# 12_-_REFERENCE_CLOCKS.net
KiCad netlist of a schematic drawn in Altium Designer
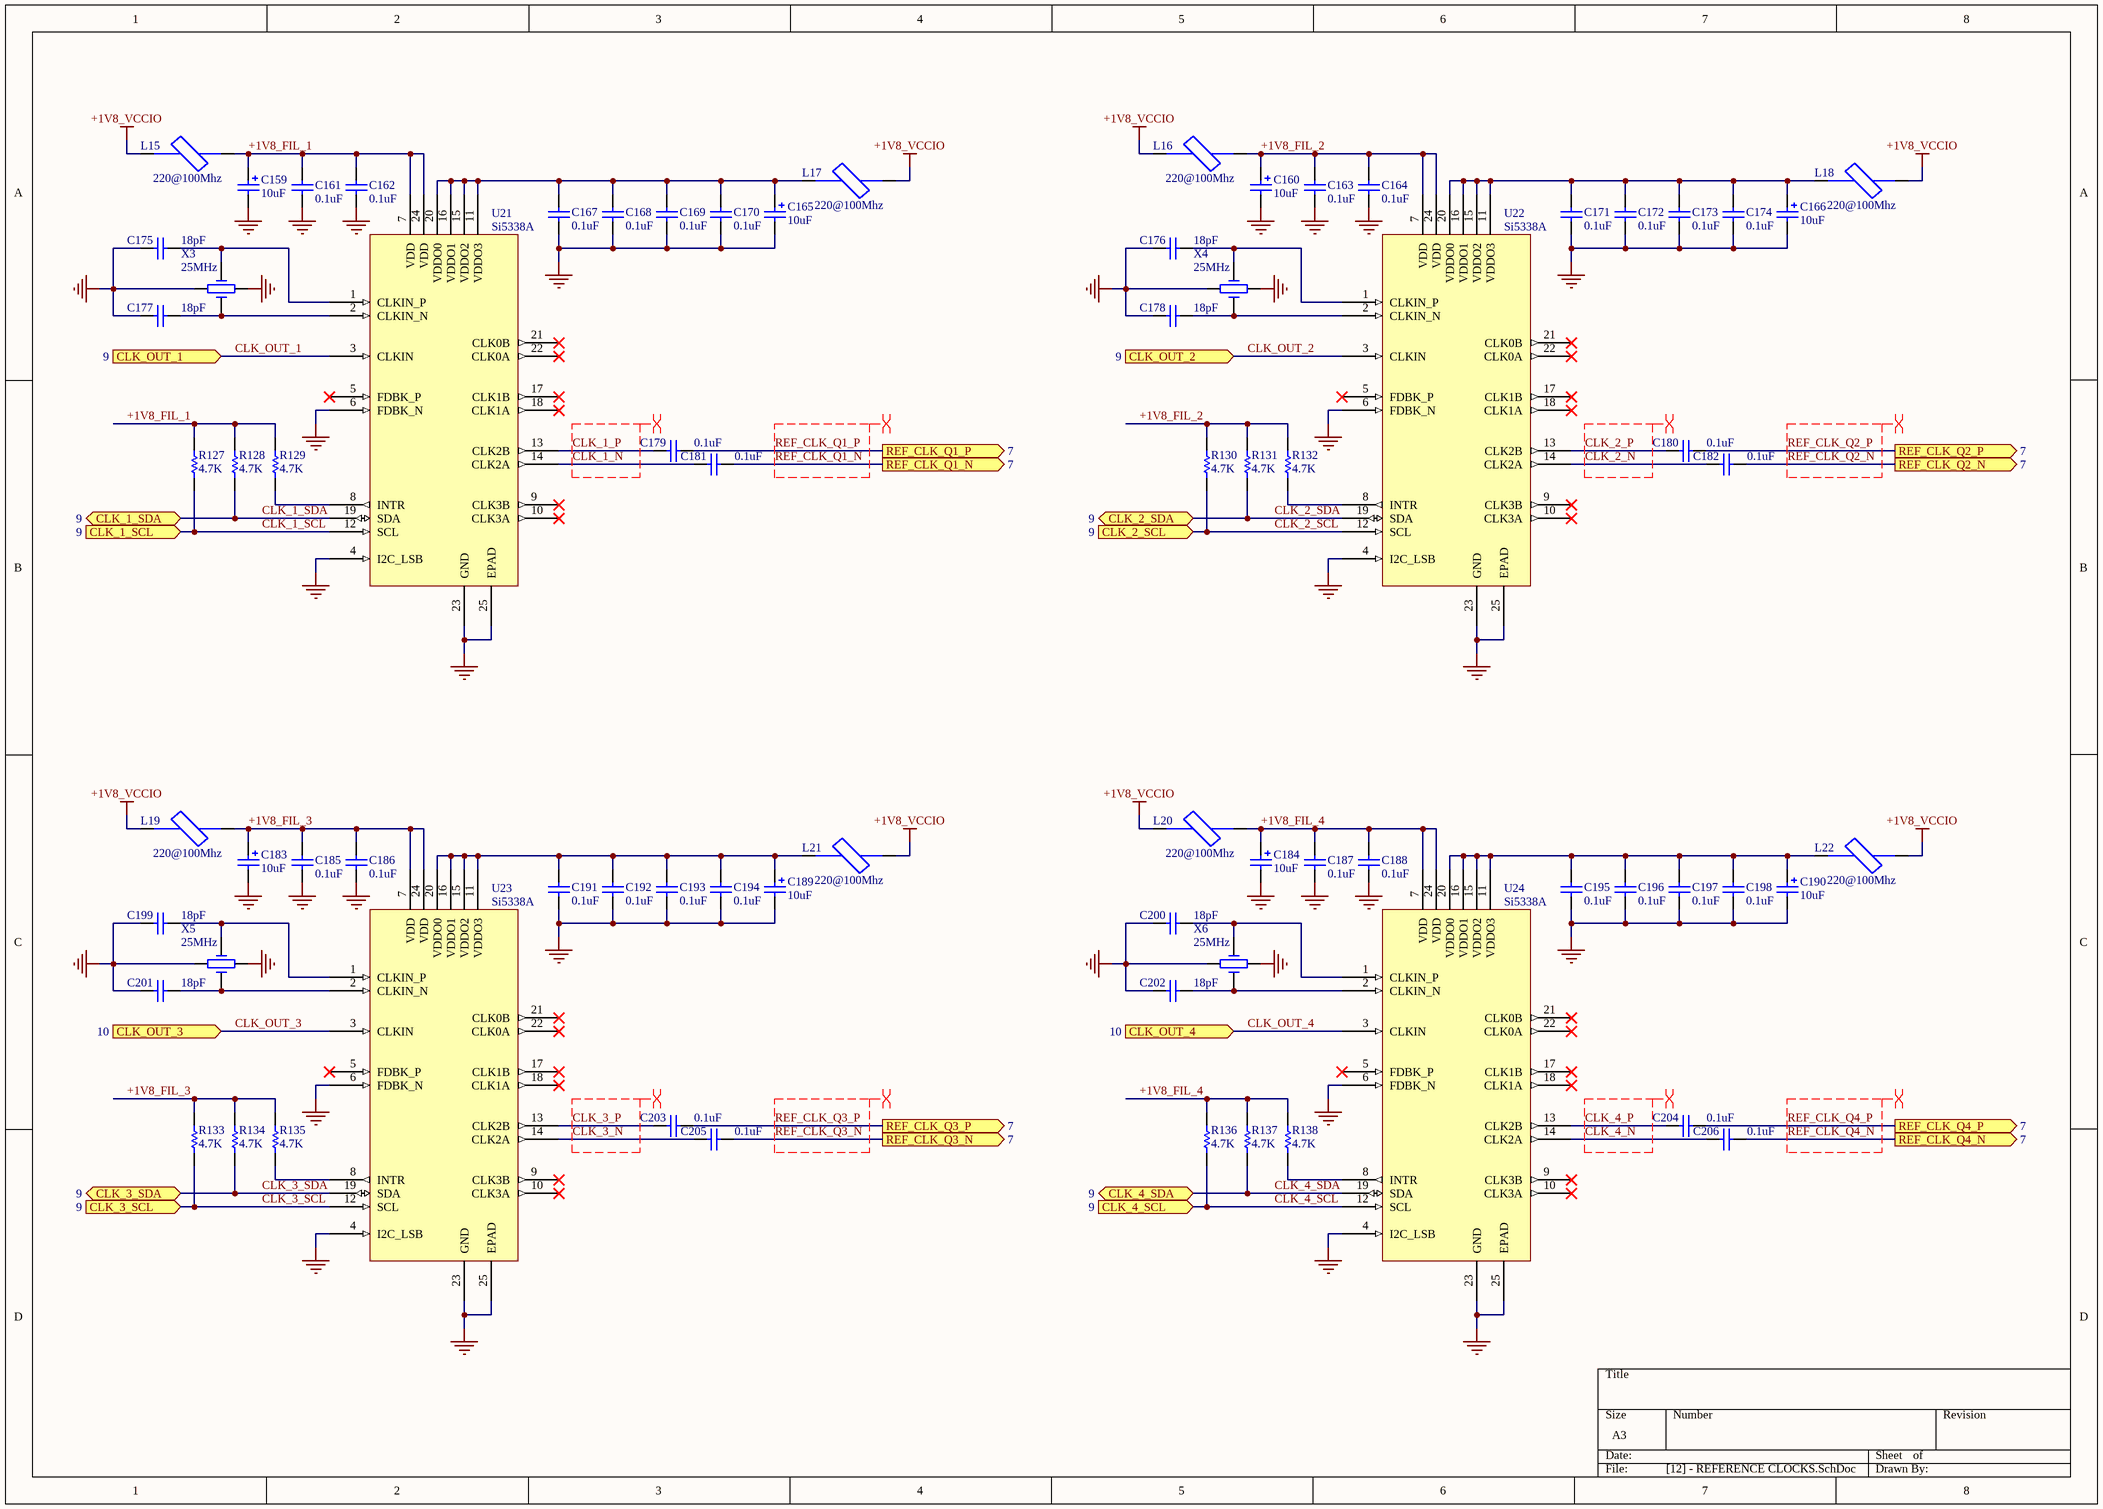
[diagram p0: [12] - REFERENCE CLOCKS.SchDoc]

(export (version "E")
  (design (tool "Eeschema 10.0.6"))
  (components
    (comp (ref "C159")
      (value "10uF")
      (footprint "TANT_B")
      (description "Tantalum Polarized Capacitor")
      (libsource (lib "Passive Components") (part "Cap Tant"))
    )
    (comp (ref "C160")
      (value "10uF")
      (footprint "TANT_B")
      (description "Tantalum Polarized Capacitor")
      (libsource (lib "Passive Components") (part "Cap Tant"))
    )
    (comp (ref "C161")
      (value "0.1uF")
      (footprint "0402_C")
      (description "Non-Pol SMD Capacitor")
      (libsource (lib "Passive Components") (part "Cap SMD"))
    )
    (comp (ref "C162")
      (value "0.1uF")
      (footprint "0402_C")
      (description "Non-Pol SMD Capacitor")
      (libsource (lib "Passive Components") (part "Cap SMD"))
    )
    (comp (ref "C163")
      (value "0.1uF")
      (footprint "0402_C")
      (description "Non-Pol SMD Capacitor")
      (libsource (lib "Passive Components") (part "Cap SMD"))
    )
    (comp (ref "C164")
      (value "0.1uF")
      (footprint "0402_C")
      (description "Non-Pol SMD Capacitor")
      (libsource (lib "Passive Components") (part "Cap SMD"))
    )
    (comp (ref "C165")
      (value "10uF")
      (footprint "TANT_B")
      (description "Tantalum Polarized Capacitor")
      (libsource (lib "Passive Components") (part "Cap Tant"))
    )
    (comp (ref "C166")
      (value "10uF")
      (footprint "TANT_B")
      (description "Tantalum Polarized Capacitor")
      (libsource (lib "Passive Components") (part "Cap Tant"))
    )
    (comp (ref "C167")
      (value "0.1uF")
      (footprint "0402_C")
      (description "Non-Pol SMD Capacitor")
      (libsource (lib "Passive Components") (part "Cap SMD"))
    )
    (comp (ref "C168")
      (value "0.1uF")
      (footprint "0402_C")
      (description "Non-Pol SMD Capacitor")
      (libsource (lib "Passive Components") (part "Cap SMD"))
    )
    (comp (ref "C169")
      (value "0.1uF")
      (footprint "0402_C")
      (description "Non-Pol SMD Capacitor")
      (libsource (lib "Passive Components") (part "Cap SMD"))
    )
    (comp (ref "C170")
      (value "0.1uF")
      (footprint "0402_C")
      (description "Non-Pol SMD Capacitor")
      (libsource (lib "Passive Components") (part "Cap SMD"))
    )
    (comp (ref "C171")
      (value "0.1uF")
      (footprint "0402_C")
      (description "Non-Pol SMD Capacitor")
      (libsource (lib "Passive Components") (part "Cap SMD"))
    )
    (comp (ref "C172")
      (value "0.1uF")
      (footprint "0402_C")
      (description "Non-Pol SMD Capacitor")
      (libsource (lib "Passive Components") (part "Cap SMD"))
    )
    (comp (ref "C173")
      (value "0.1uF")
      (footprint "0402_C")
      (description "Non-Pol SMD Capacitor")
      (libsource (lib "Passive Components") (part "Cap SMD"))
    )
    (comp (ref "C174")
      (value "0.1uF")
      (footprint "0402_C")
      (description "Non-Pol SMD Capacitor")
      (libsource (lib "Passive Components") (part "Cap SMD"))
    )
    (comp (ref "C175")
      (value "18pF")
      (footprint "0402_C")
      (description "Non-Pol SMD Capacitor")
      (libsource (lib "Passive Components") (part "Cap SMD"))
    )
    (comp (ref "C176")
      (value "18pF")
      (footprint "0402_C")
      (description "Non-Pol SMD Capacitor")
      (libsource (lib "Passive Components") (part "Cap SMD"))
    )
    (comp (ref "C177")
      (value "18pF")
      (footprint "0402_C")
      (description "Non-Pol SMD Capacitor")
      (libsource (lib "Passive Components") (part "Cap SMD"))
    )
    (comp (ref "C178")
      (value "18pF")
      (footprint "0402_C")
      (description "Non-Pol SMD Capacitor")
      (libsource (lib "Passive Components") (part "Cap SMD"))
    )
    (comp (ref "C179")
      (value "0.1uF")
      (footprint "0402_C")
      (description "Non-Pol SMD Capacitor")
      (libsource (lib "Passive Components") (part "Cap SMD"))
    )
    (comp (ref "C180")
      (value "0.1uF")
      (footprint "0402_C")
      (description "Non-Pol SMD Capacitor")
      (libsource (lib "Passive Components") (part "Cap SMD"))
    )
    (comp (ref "C181")
      (value "0.1uF")
      (footprint "0402_C")
      (description "Non-Pol SMD Capacitor")
      (libsource (lib "Passive Components") (part "Cap SMD"))
    )
    (comp (ref "C182")
      (value "0.1uF")
      (footprint "0402_C")
      (description "Non-Pol SMD Capacitor")
      (libsource (lib "Passive Components") (part "Cap SMD"))
    )
    (comp (ref "C183")
      (value "10uF")
      (footprint "TANT_B")
      (description "Tantalum Polarized Capacitor")
      (libsource (lib "Passive Components") (part "Cap Tant"))
    )
    (comp (ref "C184")
      (value "10uF")
      (footprint "TANT_B")
      (description "Tantalum Polarized Capacitor")
      (libsource (lib "Passive Components") (part "Cap Tant"))
    )
    (comp (ref "C185")
      (value "0.1uF")
      (footprint "0402_C")
      (description "Non-Pol SMD Capacitor")
      (libsource (lib "Passive Components") (part "Cap SMD"))
    )
    (comp (ref "C186")
      (value "0.1uF")
      (footprint "0402_C")
      (description "Non-Pol SMD Capacitor")
      (libsource (lib "Passive Components") (part "Cap SMD"))
    )
    (comp (ref "C187")
      (value "0.1uF")
      (footprint "0402_C")
      (description "Non-Pol SMD Capacitor")
      (libsource (lib "Passive Components") (part "Cap SMD"))
    )
    (comp (ref "C188")
      (value "0.1uF")
      (footprint "0402_C")
      (description "Non-Pol SMD Capacitor")
      (libsource (lib "Passive Components") (part "Cap SMD"))
    )
    (comp (ref "C189")
      (value "10uF")
      (footprint "TANT_B")
      (description "Tantalum Polarized Capacitor")
      (libsource (lib "Passive Components") (part "Cap Tant"))
    )
    (comp (ref "C190")
      (value "10uF")
      (footprint "TANT_B")
      (description "Tantalum Polarized Capacitor")
      (libsource (lib "Passive Components") (part "Cap Tant"))
    )
    (comp (ref "C191")
      (value "0.1uF")
      (footprint "0402_C")
      (description "Non-Pol SMD Capacitor")
      (libsource (lib "Passive Components") (part "Cap SMD"))
    )
    (comp (ref "C192")
      (value "0.1uF")
      (footprint "0402_C")
      (description "Non-Pol SMD Capacitor")
      (libsource (lib "Passive Components") (part "Cap SMD"))
    )
    (comp (ref "C193")
      (value "0.1uF")
      (footprint "0402_C")
      (description "Non-Pol SMD Capacitor")
      (libsource (lib "Passive Components") (part "Cap SMD"))
    )
    (comp (ref "C194")
      (value "0.1uF")
      (footprint "0402_C")
      (description "Non-Pol SMD Capacitor")
      (libsource (lib "Passive Components") (part "Cap SMD"))
    )
    (comp (ref "C195")
      (value "0.1uF")
      (footprint "0402_C")
      (description "Non-Pol SMD Capacitor")
      (libsource (lib "Passive Components") (part "Cap SMD"))
    )
    (comp (ref "C196")
      (value "0.1uF")
      (footprint "0402_C")
      (description "Non-Pol SMD Capacitor")
      (libsource (lib "Passive Components") (part "Cap SMD"))
    )
    (comp (ref "C197")
      (value "0.1uF")
      (footprint "0402_C")
      (description "Non-Pol SMD Capacitor")
      (libsource (lib "Passive Components") (part "Cap SMD"))
    )
    (comp (ref "C198")
      (value "0.1uF")
      (footprint "0402_C")
      (description "Non-Pol SMD Capacitor")
      (libsource (lib "Passive Components") (part "Cap SMD"))
    )
    (comp (ref "C199")
      (value "18pF")
      (footprint "0402_C")
      (description "Non-Pol SMD Capacitor")
      (libsource (lib "Passive Components") (part "Cap SMD"))
    )
    (comp (ref "C200")
      (value "18pF")
      (footprint "0402_C")
      (description "Non-Pol SMD Capacitor")
      (libsource (lib "Passive Components") (part "Cap SMD"))
    )
    (comp (ref "C201")
      (value "18pF")
      (footprint "0402_C")
      (description "Non-Pol SMD Capacitor")
      (libsource (lib "Passive Components") (part "Cap SMD"))
    )
    (comp (ref "C202")
      (value "18pF")
      (footprint "0402_C")
      (description "Non-Pol SMD Capacitor")
      (libsource (lib "Passive Components") (part "Cap SMD"))
    )
    (comp (ref "C203")
      (value "0.1uF")
      (footprint "0402_C")
      (description "Non-Pol SMD Capacitor")
      (libsource (lib "Passive Components") (part "Cap SMD"))
    )
    (comp (ref "C204")
      (value "0.1uF")
      (footprint "0402_C")
      (description "Non-Pol SMD Capacitor")
      (libsource (lib "Passive Components") (part "Cap SMD"))
    )
    (comp (ref "C205")
      (value "0.1uF")
      (footprint "0402_C")
      (description "Non-Pol SMD Capacitor")
      (libsource (lib "Passive Components") (part "Cap SMD"))
    )
    (comp (ref "C206")
      (value "0.1uF")
      (footprint "0402_C")
      (description "Non-Pol SMD Capacitor")
      (libsource (lib "Passive Components") (part "Cap SMD"))
    )
    (comp (ref "L15")
      (value "220@100Mhz")
      (footprint "0805_L")
      (description "Ferrite Bead")
      (libsource (lib "Passive Components") (part "Ferrite Bead"))
    )
    (comp (ref "L16")
      (value "220@100Mhz")
      (footprint "0805_L")
      (description "Ferrite Bead")
      (libsource (lib "Passive Components") (part "Ferrite Bead"))
    )
    (comp (ref "L17")
      (value "220@100Mhz")
      (footprint "0805_L")
      (description "Ferrite Bead")
      (libsource (lib "Passive Components") (part "Ferrite Bead"))
    )
    (comp (ref "L18")
      (value "220@100Mhz")
      (footprint "0805_L")
      (description "Ferrite Bead")
      (libsource (lib "Passive Components") (part "Ferrite Bead"))
    )
    (comp (ref "L19")
      (value "220@100Mhz")
      (footprint "0805_L")
      (description "Ferrite Bead")
      (libsource (lib "Passive Components") (part "Ferrite Bead"))
    )
    (comp (ref "L20")
      (value "220@100Mhz")
      (footprint "0805_L")
      (description "Ferrite Bead")
      (libsource (lib "Passive Components") (part "Ferrite Bead"))
    )
    (comp (ref "L21")
      (value "220@100Mhz")
      (footprint "0805_L")
      (description "Ferrite Bead")
      (libsource (lib "Passive Components") (part "Ferrite Bead"))
    )
    (comp (ref "L22")
      (value "220@100Mhz")
      (footprint "0805_L")
      (description "Ferrite Bead")
      (libsource (lib "Passive Components") (part "Ferrite Bead"))
    )
    (comp (ref "R127")
      (value "4.7K")
      (footprint "0402_R")
      (description "SMD Resistor")
      (fields (field (name "TOLERANCE") "5%"))
      (libsource (lib "Passive Components") (part "Res SMD"))
    )
    (comp (ref "R128")
      (value "4.7K")
      (footprint "0402_R")
      (description "SMD Resistor")
      (fields (field (name "TOLERANCE") "5%"))
      (libsource (lib "Passive Components") (part "Res SMD"))
    )
    (comp (ref "R129")
      (value "4.7K")
      (footprint "0402_R")
      (description "SMD Resistor")
      (fields (field (name "TOLERANCE") "5%"))
      (libsource (lib "Passive Components") (part "Res SMD"))
    )
    (comp (ref "R130")
      (value "4.7K")
      (footprint "0402_R")
      (description "SMD Resistor")
      (fields (field (name "TOLERANCE") "5%"))
      (libsource (lib "Passive Components") (part "Res SMD"))
    )
    (comp (ref "R131")
      (value "4.7K")
      (footprint "0402_R")
      (description "SMD Resistor")
      (fields (field (name "TOLERANCE") "5%"))
      (libsource (lib "Passive Components") (part "Res SMD"))
    )
    (comp (ref "R132")
      (value "4.7K")
      (footprint "0402_R")
      (description "SMD Resistor")
      (fields (field (name "TOLERANCE") "5%"))
      (libsource (lib "Passive Components") (part "Res SMD"))
    )
    (comp (ref "R133")
      (value "4.7K")
      (footprint "0402_R")
      (description "SMD Resistor")
      (fields (field (name "TOLERANCE") "5%"))
      (libsource (lib "Passive Components") (part "Res SMD"))
    )
    (comp (ref "R134")
      (value "4.7K")
      (footprint "0402_R")
      (description "SMD Resistor")
      (fields (field (name "TOLERANCE") "5%"))
      (libsource (lib "Passive Components") (part "Res SMD"))
    )
    (comp (ref "R135")
      (value "4.7K")
      (footprint "0402_R")
      (description "SMD Resistor")
      (fields (field (name "TOLERANCE") "5%"))
      (libsource (lib "Passive Components") (part "Res SMD"))
    )
    (comp (ref "R136")
      (value "4.7K")
      (footprint "0402_R")
      (description "SMD Resistor")
      (fields (field (name "TOLERANCE") "5%"))
      (libsource (lib "Passive Components") (part "Res SMD"))
    )
    (comp (ref "R137")
      (value "4.7K")
      (footprint "0402_R")
      (description "SMD Resistor")
      (fields (field (name "TOLERANCE") "5%"))
      (libsource (lib "Passive Components") (part "Res SMD"))
    )
    (comp (ref "R138")
      (value "4.7K")
      (footprint "0402_R")
      (description "SMD Resistor")
      (fields (field (name "TOLERANCE") "5%"))
      (libsource (lib "Passive Components") (part "Res SMD"))
    )
    (comp (ref "U21")
      (value "Si5338A")
      (description "I2C-Programmable Any-Frequency, Any-Output Quad Clock Generator")
      (libsource (lib "Project_schlib") (part "Si5338"))
    )
    (comp (ref "U22")
      (value "Si5338A")
      (description "I2C-Programmable Any-Frequency, Any-Output Quad Clock Generator")
      (libsource (lib "Project_schlib") (part "Si5338"))
    )
    (comp (ref "U23")
      (value "Si5338A")
      (description "I2C-Programmable Any-Frequency, Any-Output Quad Clock Generator")
      (libsource (lib "Project_schlib") (part "Si5338"))
    )
    (comp (ref "U24")
      (value "Si5338A")
      (description "I2C-Programmable Any-Frequency, Any-Output Quad Clock Generator")
      (libsource (lib "Project_schlib") (part "Si5338"))
    )
    (comp (ref "X3")
      (value "25MHz")
      (footprint "OSC_3.2x2.5")
      (description "4-pin SMD Crystal")
      (fields (field (name "MANUFACTURER PART NUM") "ABM3B-25.000MHZ-D2Y-T"))
      (libsource (lib "Common Components") (part "XTAL 4pin"))
    )
    (comp (ref "X4")
      (value "25MHz")
      (footprint "OSC_3.2x2.5")
      (description "4-pin SMD Crystal")
      (fields (field (name "MANUFACTURER PART NUM") "ABM3B-25.000MHZ-D2Y-T"))
      (libsource (lib "Common Components") (part "XTAL 4pin"))
    )
    (comp (ref "X5")
      (value "25MHz")
      (footprint "OSC_3.2x2.5")
      (description "4-pin SMD Crystal")
      (fields (field (name "MANUFACTURER PART NUM") "ABM3B-25.000MHZ-D2Y-T"))
      (libsource (lib "Common Components") (part "XTAL 4pin"))
    )
    (comp (ref "X6")
      (value "25MHz")
      (footprint "OSC_3.2x2.5")
      (description "4-pin SMD Crystal")
      (fields (field (name "MANUFACTURER PART NUM") "ABM3B-25.000MHZ-D2Y-T"))
      (libsource (lib "Common Components") (part "XTAL 4pin"))
    )
  )
  (nets
    (net (code "1") (name "+1V8_VCCIO") (class "Default")
      (node (ref "L15") (pin "1") (pinfunction "1_1") (pintype "passive"))
      (node (ref "L16") (pin "1") (pinfunction "1_1") (pintype "passive"))
      (node (ref "L17") (pin "2") (pinfunction "2_2") (pintype "passive"))
      (node (ref "L18") (pin "2") (pinfunction "2_2") (pintype "passive"))
      (node (ref "L19") (pin "1") (pinfunction "1_1") (pintype "passive"))
      (node (ref "L20") (pin "1") (pinfunction "1_1") (pintype "passive"))
      (node (ref "L21") (pin "2") (pinfunction "2_2") (pintype "passive"))
      (node (ref "L22") (pin "2") (pinfunction "2_2") (pintype "passive"))
    )
    (net (code "2") (name "/+1V8_FIL_1") (class "Default")
      (node (ref "C159") (pin "1") (pinfunction "1_1") (pintype "passive"))
      (node (ref "C161") (pin "2") (pinfunction "2_2") (pintype "passive"))
      (node (ref "C162") (pin "2") (pinfunction "2_2") (pintype "passive"))
      (node (ref "L15") (pin "2") (pinfunction "2_2") (pintype "passive"))
      (node (ref "R127") (pin "2") (pinfunction "2_2") (pintype "passive"))
      (node (ref "R128") (pin "2") (pinfunction "2_2") (pintype "passive"))
      (node (ref "R129") (pin "2") (pinfunction "2_2") (pintype "passive"))
      (node (ref "U21") (pin "24") (pinfunction "VDD_24") (pintype "power_in"))
      (node (ref "U21") (pin "7") (pinfunction "VDD_7") (pintype "power_in"))
    )
    (net (code "3") (name "/+1V8_FIL_2") (class "Default")
      (node (ref "C160") (pin "1") (pinfunction "1_1") (pintype "passive"))
      (node (ref "C163") (pin "2") (pinfunction "2_2") (pintype "passive"))
      (node (ref "C164") (pin "2") (pinfunction "2_2") (pintype "passive"))
      (node (ref "L16") (pin "2") (pinfunction "2_2") (pintype "passive"))
      (node (ref "R130") (pin "2") (pinfunction "2_2") (pintype "passive"))
      (node (ref "R131") (pin "2") (pinfunction "2_2") (pintype "passive"))
      (node (ref "R132") (pin "2") (pinfunction "2_2") (pintype "passive"))
      (node (ref "U22") (pin "24") (pinfunction "VDD_24") (pintype "power_in"))
      (node (ref "U22") (pin "7") (pinfunction "VDD_7") (pintype "power_in"))
    )
    (net (code "4") (name "/+1V8_FIL_3") (class "Default")
      (node (ref "C183") (pin "1") (pinfunction "1_1") (pintype "passive"))
      (node (ref "C185") (pin "2") (pinfunction "2_2") (pintype "passive"))
      (node (ref "C186") (pin "2") (pinfunction "2_2") (pintype "passive"))
      (node (ref "L19") (pin "2") (pinfunction "2_2") (pintype "passive"))
      (node (ref "R133") (pin "2") (pinfunction "2_2") (pintype "passive"))
      (node (ref "R134") (pin "2") (pinfunction "2_2") (pintype "passive"))
      (node (ref "R135") (pin "2") (pinfunction "2_2") (pintype "passive"))
      (node (ref "U23") (pin "24") (pinfunction "VDD_24") (pintype "power_in"))
      (node (ref "U23") (pin "7") (pinfunction "VDD_7") (pintype "power_in"))
    )
    (net (code "5") (name "/+1V8_FIL_4") (class "Default")
      (node (ref "C184") (pin "1") (pinfunction "1_1") (pintype "passive"))
      (node (ref "C187") (pin "2") (pinfunction "2_2") (pintype "passive"))
      (node (ref "C188") (pin "2") (pinfunction "2_2") (pintype "passive"))
      (node (ref "L20") (pin "2") (pinfunction "2_2") (pintype "passive"))
      (node (ref "R136") (pin "2") (pinfunction "2_2") (pintype "passive"))
      (node (ref "R137") (pin "2") (pinfunction "2_2") (pintype "passive"))
      (node (ref "R138") (pin "2") (pinfunction "2_2") (pintype "passive"))
      (node (ref "U24") (pin "24") (pinfunction "VDD_24") (pintype "power_in"))
      (node (ref "U24") (pin "7") (pinfunction "VDD_7") (pintype "power_in"))
    )
    (net (code "6") (name "/CLK_1_N") (class "Default")
      (node (ref "C181") (pin "1") (pinfunction "1_1") (pintype "passive"))
      (node (ref "U21") (pin "14") (pinfunction "CLK2A_14") (pintype "output"))
    )
    (net (code "7") (name "/CLK_1_P") (class "Default")
      (node (ref "C179") (pin "1") (pinfunction "1_1") (pintype "passive"))
      (node (ref "U21") (pin "13") (pinfunction "CLK2B_13") (pintype "output"))
    )
    (net (code "8") (name "/CLK_1_SCL") (class "Default")
      (node (ref "R127") (pin "1") (pinfunction "1_1") (pintype "passive"))
      (node (ref "U21") (pin "12") (pinfunction "SCL_12") (pintype "input"))
    )
    (net (code "9") (name "/CLK_1_SDA") (class "Default")
      (node (ref "R128") (pin "1") (pinfunction "1_1") (pintype "passive"))
      (node (ref "U21") (pin "19") (pinfunction "SDA_19") (pintype "bidirectional"))
    )
    (net (code "10") (name "/CLK_2_N") (class "Default")
      (node (ref "C182") (pin "1") (pinfunction "1_1") (pintype "passive"))
      (node (ref "U22") (pin "14") (pinfunction "CLK2A_14") (pintype "output"))
    )
    (net (code "11") (name "/CLK_2_P") (class "Default")
      (node (ref "C180") (pin "1") (pinfunction "1_1") (pintype "passive"))
      (node (ref "U22") (pin "13") (pinfunction "CLK2B_13") (pintype "output"))
    )
    (net (code "12") (name "/CLK_2_SCL") (class "Default")
      (node (ref "R130") (pin "1") (pinfunction "1_1") (pintype "passive"))
      (node (ref "U22") (pin "12") (pinfunction "SCL_12") (pintype "input"))
    )
    (net (code "13") (name "/CLK_2_SDA") (class "Default")
      (node (ref "R131") (pin "1") (pinfunction "1_1") (pintype "passive"))
      (node (ref "U22") (pin "19") (pinfunction "SDA_19") (pintype "bidirectional"))
    )
    (net (code "14") (name "/CLK_3_N") (class "Default")
      (node (ref "C205") (pin "1") (pinfunction "1_1") (pintype "passive"))
      (node (ref "U23") (pin "14") (pinfunction "CLK2A_14") (pintype "output"))
    )
    (net (code "15") (name "/CLK_3_P") (class "Default")
      (node (ref "C203") (pin "1") (pinfunction "1_1") (pintype "passive"))
      (node (ref "U23") (pin "13") (pinfunction "CLK2B_13") (pintype "output"))
    )
    (net (code "16") (name "/CLK_3_SCL") (class "Default")
      (node (ref "R133") (pin "1") (pinfunction "1_1") (pintype "passive"))
      (node (ref "U23") (pin "12") (pinfunction "SCL_12") (pintype "input"))
    )
    (net (code "17") (name "/CLK_3_SDA") (class "Default")
      (node (ref "R134") (pin "1") (pinfunction "1_1") (pintype "passive"))
      (node (ref "U23") (pin "19") (pinfunction "SDA_19") (pintype "bidirectional"))
    )
    (net (code "18") (name "/CLK_4_N") (class "Default")
      (node (ref "C206") (pin "1") (pinfunction "1_1") (pintype "passive"))
      (node (ref "U24") (pin "14") (pinfunction "CLK2A_14") (pintype "output"))
    )
    (net (code "19") (name "/CLK_4_P") (class "Default")
      (node (ref "C204") (pin "1") (pinfunction "1_1") (pintype "passive"))
      (node (ref "U24") (pin "13") (pinfunction "CLK2B_13") (pintype "output"))
    )
    (net (code "20") (name "/CLK_4_SCL") (class "Default")
      (node (ref "R136") (pin "1") (pinfunction "1_1") (pintype "passive"))
      (node (ref "U24") (pin "12") (pinfunction "SCL_12") (pintype "input"))
    )
    (net (code "21") (name "/CLK_4_SDA") (class "Default")
      (node (ref "R137") (pin "1") (pinfunction "1_1") (pintype "passive"))
      (node (ref "U24") (pin "19") (pinfunction "SDA_19") (pintype "bidirectional"))
    )
    (net (code "22") (name "/CLK_OUT_1") (class "Default")
      (node (ref "U21") (pin "3") (pinfunction "CLKIN_3") (pintype "input"))
    )
    (net (code "23") (name "/CLK_OUT_2") (class "Default")
      (node (ref "U22") (pin "3") (pinfunction "CLKIN_3") (pintype "input"))
    )
    (net (code "24") (name "/CLK_OUT_3") (class "Default")
      (node (ref "U23") (pin "3") (pinfunction "CLKIN_3") (pintype "input"))
    )
    (net (code "25") (name "/CLK_OUT_4") (class "Default")
      (node (ref "U24") (pin "3") (pinfunction "CLKIN_3") (pintype "input"))
    )
    (net (code "26") (name "/REF_CLK_Q1_N") (class "Default")
      (node (ref "C181") (pin "2") (pinfunction "2_2") (pintype "passive"))
    )
    (net (code "27") (name "/REF_CLK_Q1_P") (class "Default")
      (node (ref "C179") (pin "2") (pinfunction "2_2") (pintype "passive"))
    )
    (net (code "28") (name "/REF_CLK_Q2_N") (class "Default")
      (node (ref "C182") (pin "2") (pinfunction "2_2") (pintype "passive"))
    )
    (net (code "29") (name "/REF_CLK_Q2_P") (class "Default")
      (node (ref "C180") (pin "2") (pinfunction "2_2") (pintype "passive"))
    )
    (net (code "30") (name "/REF_CLK_Q3_N") (class "Default")
      (node (ref "C205") (pin "2") (pinfunction "2_2") (pintype "passive"))
    )
    (net (code "31") (name "/REF_CLK_Q3_P") (class "Default")
      (node (ref "C203") (pin "2") (pinfunction "2_2") (pintype "passive"))
    )
    (net (code "32") (name "/REF_CLK_Q4_N") (class "Default")
      (node (ref "C206") (pin "2") (pinfunction "2_2") (pintype "passive"))
    )
    (net (code "33") (name "/REF_CLK_Q4_P") (class "Default")
      (node (ref "C204") (pin "2") (pinfunction "2_2") (pintype "passive"))
    )
    (net (code "34") (name "GND") (class "Default")
      (node (ref "C159") (pin "2") (pinfunction "2_2") (pintype "passive"))
      (node (ref "C160") (pin "2") (pinfunction "2_2") (pintype "passive"))
      (node (ref "C161") (pin "1") (pinfunction "1_1") (pintype "passive"))
      (node (ref "C162") (pin "1") (pinfunction "1_1") (pintype "passive"))
      (node (ref "C163") (pin "1") (pinfunction "1_1") (pintype "passive"))
      (node (ref "C164") (pin "1") (pinfunction "1_1") (pintype "passive"))
      (node (ref "C165") (pin "2") (pinfunction "2_2") (pintype "passive"))
      (node (ref "C166") (pin "2") (pinfunction "2_2") (pintype "passive"))
      (node (ref "C167") (pin "1") (pinfunction "1_1") (pintype "passive"))
      (node (ref "C168") (pin "1") (pinfunction "1_1") (pintype "passive"))
      (node (ref "C169") (pin "1") (pinfunction "1_1") (pintype "passive"))
      (node (ref "C170") (pin "1") (pinfunction "1_1") (pintype "passive"))
      (node (ref "C171") (pin "1") (pinfunction "1_1") (pintype "passive"))
      (node (ref "C172") (pin "1") (pinfunction "1_1") (pintype "passive"))
      (node (ref "C173") (pin "1") (pinfunction "1_1") (pintype "passive"))
      (node (ref "C174") (pin "1") (pinfunction "1_1") (pintype "passive"))
      (node (ref "C175") (pin "1") (pinfunction "1_1") (pintype "passive"))
      (node (ref "C176") (pin "1") (pinfunction "1_1") (pintype "passive"))
      (node (ref "C177") (pin "1") (pinfunction "1_1") (pintype "passive"))
      (node (ref "C178") (pin "1") (pinfunction "1_1") (pintype "passive"))
      (node (ref "C183") (pin "2") (pinfunction "2_2") (pintype "passive"))
      (node (ref "C184") (pin "2") (pinfunction "2_2") (pintype "passive"))
      (node (ref "C185") (pin "1") (pinfunction "1_1") (pintype "passive"))
      (node (ref "C186") (pin "1") (pinfunction "1_1") (pintype "passive"))
      (node (ref "C187") (pin "1") (pinfunction "1_1") (pintype "passive"))
      (node (ref "C188") (pin "1") (pinfunction "1_1") (pintype "passive"))
      (node (ref "C189") (pin "2") (pinfunction "2_2") (pintype "passive"))
      (node (ref "C190") (pin "2") (pinfunction "2_2") (pintype "passive"))
      (node (ref "C191") (pin "1") (pinfunction "1_1") (pintype "passive"))
      (node (ref "C192") (pin "1") (pinfunction "1_1") (pintype "passive"))
      (node (ref "C193") (pin "1") (pinfunction "1_1") (pintype "passive"))
      (node (ref "C194") (pin "1") (pinfunction "1_1") (pintype "passive"))
      (node (ref "C195") (pin "1") (pinfunction "1_1") (pintype "passive"))
      (node (ref "C196") (pin "1") (pinfunction "1_1") (pintype "passive"))
      (node (ref "C197") (pin "1") (pinfunction "1_1") (pintype "passive"))
      (node (ref "C198") (pin "1") (pinfunction "1_1") (pintype "passive"))
      (node (ref "C199") (pin "1") (pinfunction "1_1") (pintype "passive"))
      (node (ref "C200") (pin "1") (pinfunction "1_1") (pintype "passive"))
      (node (ref "C201") (pin "1") (pinfunction "1_1") (pintype "passive"))
      (node (ref "C202") (pin "1") (pinfunction "1_1") (pintype "passive"))
      (node (ref "U21") (pin "23") (pinfunction "GND_23") (pintype "power_in"))
      (node (ref "U21") (pin "25") (pinfunction "EPAD_25") (pintype "power_in"))
      (node (ref "U21") (pin "4") (pinfunction "I2C_LSB_4") (pintype "input"))
      (node (ref "U21") (pin "6") (pinfunction "FDBK_N_6") (pintype "input"))
      (node (ref "U22") (pin "23") (pinfunction "GND_23") (pintype "power_in"))
      (node (ref "U22") (pin "25") (pinfunction "EPAD_25") (pintype "power_in"))
      (node (ref "U22") (pin "4") (pinfunction "I2C_LSB_4") (pintype "input"))
      (node (ref "U22") (pin "6") (pinfunction "FDBK_N_6") (pintype "input"))
      (node (ref "U23") (pin "23") (pinfunction "GND_23") (pintype "power_in"))
      (node (ref "U23") (pin "25") (pinfunction "EPAD_25") (pintype "power_in"))
      (node (ref "U23") (pin "4") (pinfunction "I2C_LSB_4") (pintype "input"))
      (node (ref "U23") (pin "6") (pinfunction "FDBK_N_6") (pintype "input"))
      (node (ref "U24") (pin "23") (pinfunction "GND_23") (pintype "power_in"))
      (node (ref "U24") (pin "25") (pinfunction "EPAD_25") (pintype "power_in"))
      (node (ref "U24") (pin "4") (pinfunction "I2C_LSB_4") (pintype "input"))
      (node (ref "U24") (pin "6") (pinfunction "FDBK_N_6") (pintype "input"))
      (node (ref "X3") (pin "2") (pinfunction "GND1_2") (pintype "passive"))
      (node (ref "X3") (pin "4") (pinfunction "GND2_4") (pintype "passive"))
      (node (ref "X4") (pin "2") (pinfunction "GND1_2") (pintype "passive"))
      (node (ref "X4") (pin "4") (pinfunction "GND2_4") (pintype "passive"))
      (node (ref "X5") (pin "2") (pinfunction "GND1_2") (pintype "passive"))
      (node (ref "X5") (pin "4") (pinfunction "GND2_4") (pintype "passive"))
      (node (ref "X6") (pin "2") (pinfunction "GND1_2") (pintype "passive"))
      (node (ref "X6") (pin "4") (pinfunction "GND2_4") (pintype "passive"))
    )
    (net (code "35") (name "Net-(U21-CLKIN_N)") (class "Default")
      (node (ref "C177") (pin "2") (pinfunction "2_2") (pintype "passive"))
      (node (ref "U21") (pin "2") (pinfunction "CLKIN_N_2") (pintype "input"))
      (node (ref "X3") (pin "3") (pinfunction "OSC2_3") (pintype "passive"))
    )
    (net (code "36") (name "Net-(U21-CLKIN_P)") (class "Default")
      (node (ref "C175") (pin "2") (pinfunction "2_2") (pintype "passive"))
      (node (ref "U21") (pin "1") (pinfunction "CLKIN_P_1") (pintype "input"))
      (node (ref "X3") (pin "1") (pinfunction "OSC1_1") (pintype "passive"))
    )
    (net (code "37") (name "Net-(U21-INTR)") (class "Default")
      (node (ref "R129") (pin "1") (pinfunction "1_1") (pintype "passive"))
      (node (ref "U21") (pin "8") (pinfunction "INTR_8") (pintype "output"))
    )
    (net (code "38") (name "Net-(U21-VDDO0)") (class "Default")
      (node (ref "C165") (pin "1") (pinfunction "1_1") (pintype "passive"))
      (node (ref "C167") (pin "2") (pinfunction "2_2") (pintype "passive"))
      (node (ref "C168") (pin "2") (pinfunction "2_2") (pintype "passive"))
      (node (ref "C169") (pin "2") (pinfunction "2_2") (pintype "passive"))
      (node (ref "C170") (pin "2") (pinfunction "2_2") (pintype "passive"))
      (node (ref "L17") (pin "1") (pinfunction "1_1") (pintype "passive"))
      (node (ref "U21") (pin "11") (pinfunction "VDDO3_11") (pintype "power_in"))
      (node (ref "U21") (pin "15") (pinfunction "VDDO2_15") (pintype "power_in"))
      (node (ref "U21") (pin "16") (pinfunction "VDDO1_16") (pintype "power_in"))
      (node (ref "U21") (pin "20") (pinfunction "VDDO0_20") (pintype "power_in"))
    )
    (net (code "39") (name "Net-(U22-CLKIN_N)") (class "Default")
      (node (ref "C178") (pin "2") (pinfunction "2_2") (pintype "passive"))
      (node (ref "U22") (pin "2") (pinfunction "CLKIN_N_2") (pintype "input"))
      (node (ref "X4") (pin "3") (pinfunction "OSC2_3") (pintype "passive"))
    )
    (net (code "40") (name "Net-(U22-CLKIN_P)") (class "Default")
      (node (ref "C176") (pin "2") (pinfunction "2_2") (pintype "passive"))
      (node (ref "U22") (pin "1") (pinfunction "CLKIN_P_1") (pintype "input"))
      (node (ref "X4") (pin "1") (pinfunction "OSC1_1") (pintype "passive"))
    )
    (net (code "41") (name "Net-(U22-INTR)") (class "Default")
      (node (ref "R132") (pin "1") (pinfunction "1_1") (pintype "passive"))
      (node (ref "U22") (pin "8") (pinfunction "INTR_8") (pintype "output"))
    )
    (net (code "42") (name "Net-(U22-VDDO0)") (class "Default")
      (node (ref "C166") (pin "1") (pinfunction "1_1") (pintype "passive"))
      (node (ref "C171") (pin "2") (pinfunction "2_2") (pintype "passive"))
      (node (ref "C172") (pin "2") (pinfunction "2_2") (pintype "passive"))
      (node (ref "C173") (pin "2") (pinfunction "2_2") (pintype "passive"))
      (node (ref "C174") (pin "2") (pinfunction "2_2") (pintype "passive"))
      (node (ref "L18") (pin "1") (pinfunction "1_1") (pintype "passive"))
      (node (ref "U22") (pin "11") (pinfunction "VDDO3_11") (pintype "power_in"))
      (node (ref "U22") (pin "15") (pinfunction "VDDO2_15") (pintype "power_in"))
      (node (ref "U22") (pin "16") (pinfunction "VDDO1_16") (pintype "power_in"))
      (node (ref "U22") (pin "20") (pinfunction "VDDO0_20") (pintype "power_in"))
    )
    (net (code "43") (name "Net-(U23-CLKIN_N)") (class "Default")
      (node (ref "C201") (pin "2") (pinfunction "2_2") (pintype "passive"))
      (node (ref "U23") (pin "2") (pinfunction "CLKIN_N_2") (pintype "input"))
      (node (ref "X5") (pin "3") (pinfunction "OSC2_3") (pintype "passive"))
    )
    (net (code "44") (name "Net-(U23-CLKIN_P)") (class "Default")
      (node (ref "C199") (pin "2") (pinfunction "2_2") (pintype "passive"))
      (node (ref "U23") (pin "1") (pinfunction "CLKIN_P_1") (pintype "input"))
      (node (ref "X5") (pin "1") (pinfunction "OSC1_1") (pintype "passive"))
    )
    (net (code "45") (name "Net-(U23-INTR)") (class "Default")
      (node (ref "R135") (pin "1") (pinfunction "1_1") (pintype "passive"))
      (node (ref "U23") (pin "8") (pinfunction "INTR_8") (pintype "output"))
    )
    (net (code "46") (name "Net-(U23-VDDO0)") (class "Default")
      (node (ref "C189") (pin "1") (pinfunction "1_1") (pintype "passive"))
      (node (ref "C191") (pin "2") (pinfunction "2_2") (pintype "passive"))
      (node (ref "C192") (pin "2") (pinfunction "2_2") (pintype "passive"))
      (node (ref "C193") (pin "2") (pinfunction "2_2") (pintype "passive"))
      (node (ref "C194") (pin "2") (pinfunction "2_2") (pintype "passive"))
      (node (ref "L21") (pin "1") (pinfunction "1_1") (pintype "passive"))
      (node (ref "U23") (pin "11") (pinfunction "VDDO3_11") (pintype "power_in"))
      (node (ref "U23") (pin "15") (pinfunction "VDDO2_15") (pintype "power_in"))
      (node (ref "U23") (pin "16") (pinfunction "VDDO1_16") (pintype "power_in"))
      (node (ref "U23") (pin "20") (pinfunction "VDDO0_20") (pintype "power_in"))
    )
    (net (code "47") (name "Net-(U24-CLKIN_N)") (class "Default")
      (node (ref "C202") (pin "2") (pinfunction "2_2") (pintype "passive"))
      (node (ref "U24") (pin "2") (pinfunction "CLKIN_N_2") (pintype "input"))
      (node (ref "X6") (pin "3") (pinfunction "OSC2_3") (pintype "passive"))
    )
    (net (code "48") (name "Net-(U24-CLKIN_P)") (class "Default")
      (node (ref "C200") (pin "2") (pinfunction "2_2") (pintype "passive"))
      (node (ref "U24") (pin "1") (pinfunction "CLKIN_P_1") (pintype "input"))
      (node (ref "X6") (pin "1") (pinfunction "OSC1_1") (pintype "passive"))
    )
    (net (code "49") (name "Net-(U24-INTR)") (class "Default")
      (node (ref "R138") (pin "1") (pinfunction "1_1") (pintype "passive"))
      (node (ref "U24") (pin "8") (pinfunction "INTR_8") (pintype "output"))
    )
    (net (code "50") (name "Net-(U24-VDDO0)") (class "Default")
      (node (ref "C190") (pin "1") (pinfunction "1_1") (pintype "passive"))
      (node (ref "C195") (pin "2") (pinfunction "2_2") (pintype "passive"))
      (node (ref "C196") (pin "2") (pinfunction "2_2") (pintype "passive"))
      (node (ref "C197") (pin "2") (pinfunction "2_2") (pintype "passive"))
      (node (ref "C198") (pin "2") (pinfunction "2_2") (pintype "passive"))
      (node (ref "L22") (pin "1") (pinfunction "1_1") (pintype "passive"))
      (node (ref "U24") (pin "11") (pinfunction "VDDO3_11") (pintype "power_in"))
      (node (ref "U24") (pin "15") (pinfunction "VDDO2_15") (pintype "power_in"))
      (node (ref "U24") (pin "16") (pinfunction "VDDO1_16") (pintype "power_in"))
      (node (ref "U24") (pin "20") (pinfunction "VDDO0_20") (pintype "power_in"))
    )
    (net (code "51") (name "unconnected-(U21-CLK0A-Pad22)") (class "Default")
      (node (ref "U21") (pin "22") (pinfunction "CLK0A_22") (pintype "output+no_connect"))
    )
    (net (code "52") (name "unconnected-(U21-CLK0B-Pad21)") (class "Default")
      (node (ref "U21") (pin "21") (pinfunction "CLK0B_21") (pintype "output+no_connect"))
    )
    (net (code "53") (name "unconnected-(U21-CLK1A-Pad18)") (class "Default")
      (node (ref "U21") (pin "18") (pinfunction "CLK1A_18") (pintype "output+no_connect"))
    )
    (net (code "54") (name "unconnected-(U21-CLK1B-Pad17)") (class "Default")
      (node (ref "U21") (pin "17") (pinfunction "CLK1B_17") (pintype "output+no_connect"))
    )
    (net (code "55") (name "unconnected-(U21-CLK3A-Pad10)") (class "Default")
      (node (ref "U21") (pin "10") (pinfunction "CLK3A_10") (pintype "output+no_connect"))
    )
    (net (code "56") (name "unconnected-(U21-CLK3B-Pad9)") (class "Default")
      (node (ref "U21") (pin "9") (pinfunction "CLK3B_9") (pintype "output+no_connect"))
    )
    (net (code "57") (name "unconnected-(U21-FDBK_P-Pad5)") (class "Default")
      (node (ref "U21") (pin "5") (pinfunction "FDBK_P_5") (pintype "input+no_connect"))
    )
    (net (code "58") (name "unconnected-(U22-CLK0A-Pad22)") (class "Default")
      (node (ref "U22") (pin "22") (pinfunction "CLK0A_22") (pintype "output+no_connect"))
    )
    (net (code "59") (name "unconnected-(U22-CLK0B-Pad21)") (class "Default")
      (node (ref "U22") (pin "21") (pinfunction "CLK0B_21") (pintype "output+no_connect"))
    )
    (net (code "60") (name "unconnected-(U22-CLK1A-Pad18)") (class "Default")
      (node (ref "U22") (pin "18") (pinfunction "CLK1A_18") (pintype "output+no_connect"))
    )
    (net (code "61") (name "unconnected-(U22-CLK1B-Pad17)") (class "Default")
      (node (ref "U22") (pin "17") (pinfunction "CLK1B_17") (pintype "output+no_connect"))
    )
    (net (code "62") (name "unconnected-(U22-CLK3A-Pad10)") (class "Default")
      (node (ref "U22") (pin "10") (pinfunction "CLK3A_10") (pintype "output+no_connect"))
    )
    (net (code "63") (name "unconnected-(U22-CLK3B-Pad9)") (class "Default")
      (node (ref "U22") (pin "9") (pinfunction "CLK3B_9") (pintype "output+no_connect"))
    )
    (net (code "64") (name "unconnected-(U22-FDBK_P-Pad5)") (class "Default")
      (node (ref "U22") (pin "5") (pinfunction "FDBK_P_5") (pintype "input+no_connect"))
    )
    (net (code "65") (name "unconnected-(U23-CLK0A-Pad22)") (class "Default")
      (node (ref "U23") (pin "22") (pinfunction "CLK0A_22") (pintype "output+no_connect"))
    )
    (net (code "66") (name "unconnected-(U23-CLK0B-Pad21)") (class "Default")
      (node (ref "U23") (pin "21") (pinfunction "CLK0B_21") (pintype "output+no_connect"))
    )
    (net (code "67") (name "unconnected-(U23-CLK1A-Pad18)") (class "Default")
      (node (ref "U23") (pin "18") (pinfunction "CLK1A_18") (pintype "output+no_connect"))
    )
    (net (code "68") (name "unconnected-(U23-CLK1B-Pad17)") (class "Default")
      (node (ref "U23") (pin "17") (pinfunction "CLK1B_17") (pintype "output+no_connect"))
    )
    (net (code "69") (name "unconnected-(U23-CLK3A-Pad10)") (class "Default")
      (node (ref "U23") (pin "10") (pinfunction "CLK3A_10") (pintype "output+no_connect"))
    )
    (net (code "70") (name "unconnected-(U23-CLK3B-Pad9)") (class "Default")
      (node (ref "U23") (pin "9") (pinfunction "CLK3B_9") (pintype "output+no_connect"))
    )
    (net (code "71") (name "unconnected-(U23-FDBK_P-Pad5)") (class "Default")
      (node (ref "U23") (pin "5") (pinfunction "FDBK_P_5") (pintype "input+no_connect"))
    )
    (net (code "72") (name "unconnected-(U24-CLK0A-Pad22)") (class "Default")
      (node (ref "U24") (pin "22") (pinfunction "CLK0A_22") (pintype "output+no_connect"))
    )
    (net (code "73") (name "unconnected-(U24-CLK0B-Pad21)") (class "Default")
      (node (ref "U24") (pin "21") (pinfunction "CLK0B_21") (pintype "output+no_connect"))
    )
    (net (code "74") (name "unconnected-(U24-CLK1A-Pad18)") (class "Default")
      (node (ref "U24") (pin "18") (pinfunction "CLK1A_18") (pintype "output+no_connect"))
    )
    (net (code "75") (name "unconnected-(U24-CLK1B-Pad17)") (class "Default")
      (node (ref "U24") (pin "17") (pinfunction "CLK1B_17") (pintype "output+no_connect"))
    )
    (net (code "76") (name "unconnected-(U24-CLK3A-Pad10)") (class "Default")
      (node (ref "U24") (pin "10") (pinfunction "CLK3A_10") (pintype "output+no_connect"))
    )
    (net (code "77") (name "unconnected-(U24-CLK3B-Pad9)") (class "Default")
      (node (ref "U24") (pin "9") (pinfunction "CLK3B_9") (pintype "output+no_connect"))
    )
    (net (code "78") (name "unconnected-(U24-FDBK_P-Pad5)") (class "Default")
      (node (ref "U24") (pin "5") (pinfunction "FDBK_P_5") (pintype "input+no_connect"))
    )
  )
)
